# motion_sensor.net
KiCad netlist of a schematic drawn in Altium Designer
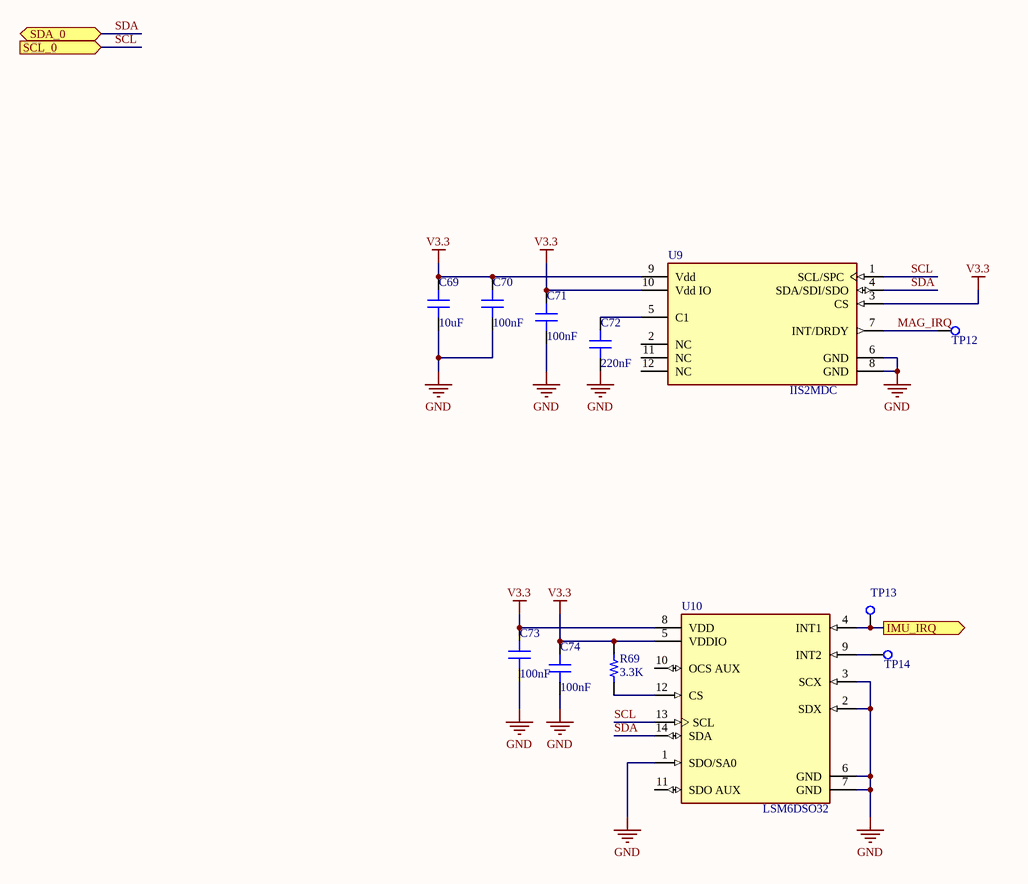
[diagram p0: motion_sensor.SchDoc]

(export (version "E")
  (design (tool "Eeschema 10.0.6"))
  (components
    (comp (ref "C69")
      (value "10uF")
      (footprint "CAP 0603_1608")
      (description "SMT Capacitor")
      (fields (field (name "MF") "Murata") (field (name "MP") "GRM188R61C106MAALD"))
      (libsource (lib "Capacitor") (part "Capacitor"))
    )
    (comp (ref "C70")
      (value "100nF")
      (footprint "CAP 0603_1608")
      (description "SMT Capacitor")
      (fields (field (name "MF") "TDK") (field (name "MP") "CGA3E2X7R1E104K080AA"))
      (libsource (lib "Capacitor") (part "Capacitor"))
    )
    (comp (ref "C71")
      (value "100nF")
      (footprint "CAP 0603_1608")
      (description "SMT Capacitor")
      (fields (field (name "MF") "TDK") (field (name "MP") "CGA3E2X7R1E104K080AA"))
      (libsource (lib "Capacitor") (part "Capacitor"))
    )
    (comp (ref "C72")
      (value "220nF")
      (footprint "CAP 0603_1608")
      (description "SMT Capacitor")
      (fields (field (name "MF") "Samsung") (field (name "MP") "CL10B224KO8NNNC"))
      (libsource (lib "Capacitor") (part "Capacitor"))
    )
    (comp (ref "C73")
      (value "100nF")
      (footprint "CAP 0603_1608")
      (description "SMT Capacitor")
      (fields (field (name "MF") "TDK") (field (name "MP") "CGA3E2X7R1E104K080AA"))
      (libsource (lib "Capacitor") (part "Capacitor"))
    )
    (comp (ref "C74")
      (value "100nF")
      (footprint "CAP 0603_1608")
      (description "SMT Capacitor")
      (fields (field (name "MF") "TDK") (field (name "MP") "CGA3E2X7R1E104K080AA"))
      (libsource (lib "Capacitor") (part "Capacitor"))
    )
    (comp (ref "R69")
      (value "3.3K")
      (footprint "RES 0603_1608")
      (description "SMT Resistor")
      (fields (field (name "MF") "YAGEO") (field (name "MP") "AC0603FR-073K3L"))
      (libsource (lib "Resistor") (part "Resistor"))
    )
    (comp (ref "TP12")
      (value "Test Point")
      (footprint "TPSMD_S1")
      (libsource (lib "Passive") (part "Test Point"))
    )
    (comp (ref "TP13")
      (value "Test Point")
      (footprint "TPSMD_S1")
      (libsource (lib "Passive") (part "Test Point"))
    )
    (comp (ref "TP14")
      (value "Test Point")
      (footprint "TPSMD_S1")
      (libsource (lib "Passive") (part "Test Point"))
    )
    (comp (ref "U9")
      (value "IIS2MDC")
      (footprint "STMicroelectronics_LGA-12-DM00170568_MFG")
      (fields (field (name "MF") "STMicroelectronics") (field (name "MP") "IIS2MDCTR"))
      (libsource (lib "IMU") (part "IIS2MDCTR"))
    )
    (comp (ref "U10")
      (value "LSM6DSO32")
      (footprint "STMicroelectronics_LGA-14L-DM00249496_MFG")
      (description "Inertial Measurement Unit, 6-axis, I2C, SPI, 1.7V-3.6V")
      (fields (field (name "MF") "STMicroelectronics") (field (name "MP") "LSM6DSO32TR"))
      (libsource (lib "IMU") (part "LSM6DSOTR"))
    )
  )
  (nets
    (net (code "1") (name "/IMU_IRQ") (class "Default")
      (node (ref "TP13") (pin "1") (pinfunction "TP_1") (pintype "passive"))
      (node (ref "U10") (pin "4") (pinfunction "INT1_4") (pintype "input"))
    )
    (net (code "2") (name "/MAG_IRQ") (class "Default")
      (node (ref "TP12") (pin "1") (pinfunction "TP_1") (pintype "passive"))
      (node (ref "U9") (pin "7") (pinfunction "INT/DRDY_7") (pintype "output"))
    )
    (net (code "3") (name "/SCL") (class "Default")
      (node (ref "U10") (pin "13") (pinfunction "SCL_13") (pintype "input"))
      (node (ref "U9") (pin "1") (pinfunction "SCL/SPC_1") (pintype "input"))
    )
    (net (code "4") (name "/SDA") (class "Default")
      (node (ref "U10") (pin "14") (pinfunction "SDA_14") (pintype "bidirectional"))
      (node (ref "U9") (pin "4") (pinfunction "SDA/SDI/SDO_4") (pintype "bidirectional"))
    )
    (net (code "5") (name "GND") (class "Default")
      (node (ref "C69") (pin "2") (pinfunction "2_2") (pintype "passive"))
      (node (ref "C70") (pin "2") (pinfunction "2_2") (pintype "passive"))
      (node (ref "C71") (pin "2") (pinfunction "2_2") (pintype "passive"))
      (node (ref "C72") (pin "2") (pinfunction "2_2") (pintype "passive"))
      (node (ref "C73") (pin "2") (pinfunction "2_2") (pintype "passive"))
      (node (ref "C74") (pin "2") (pinfunction "2_2") (pintype "passive"))
      (node (ref "U10") (pin "1") (pinfunction "SDO/SA0_1") (pintype "input"))
      (node (ref "U10") (pin "2") (pinfunction "SDX_2") (pintype "input"))
      (node (ref "U10") (pin "3") (pinfunction "SCX_3") (pintype "input"))
      (node (ref "U10") (pin "6") (pinfunction "GND_6") (pintype "power_in"))
      (node (ref "U10") (pin "7") (pinfunction "GND_7") (pintype "power_in"))
      (node (ref "U9") (pin "6") (pinfunction "GND_6") (pintype "power_in"))
      (node (ref "U9") (pin "8") (pinfunction "GND_8") (pintype "power_in"))
    )
    (net (code "6") (name "Net-(TP14-TP)") (class "Default")
      (node (ref "TP14") (pin "1") (pinfunction "TP_1") (pintype "passive"))
      (node (ref "U10") (pin "9") (pinfunction "INT2_9") (pintype "input"))
    )
    (net (code "7") (name "Net-(U9-C1)") (class "Default")
      (node (ref "C72") (pin "1") (pinfunction "1_1") (pintype "passive"))
      (node (ref "U9") (pin "5") (pinfunction "C1_5") (pintype "passive"))
    )
    (net (code "8") (name "Net-(U10-CS)") (class "Default")
      (node (ref "R69") (pin "1") (pinfunction "1_1") (pintype "passive"))
      (node (ref "U10") (pin "12") (pinfunction "CS_12") (pintype "input"))
    )
    (net (code "9") (name "V3.3") (class "Default")
      (node (ref "C69") (pin "1") (pinfunction "1_1") (pintype "passive"))
      (node (ref "C70") (pin "1") (pinfunction "1_1") (pintype "passive"))
      (node (ref "C71") (pin "1") (pinfunction "1_1") (pintype "passive"))
      (node (ref "C73") (pin "1") (pinfunction "1_1") (pintype "passive"))
      (node (ref "C74") (pin "1") (pinfunction "1_1") (pintype "passive"))
      (node (ref "R69") (pin "2") (pinfunction "2_2") (pintype "passive"))
      (node (ref "U10") (pin "5") (pinfunction "VDDIO_5") (pintype "power_in"))
      (node (ref "U10") (pin "8") (pinfunction "VDD_8") (pintype "power_in"))
      (node (ref "U9") (pin "10") (pinfunction "Vdd_IO_10") (pintype "power_in"))
      (node (ref "U9") (pin "3") (pinfunction "CS_3") (pintype "input"))
      (node (ref "U9") (pin "9") (pinfunction "Vdd_9") (pintype "power_in"))
    )
    (net (code "10") (name "unconnected-(U9-NC-Pad2)") (class "Default")
      (node (ref "U9") (pin "2") (pinfunction "NC_2") (pintype "passive"))
    )
    (net (code "11") (name "unconnected-(U9-NC-Pad11)") (class "Default")
      (node (ref "U9") (pin "11") (pinfunction "NC_11") (pintype "passive"))
    )
    (net (code "12") (name "unconnected-(U9-NC-Pad12)") (class "Default")
      (node (ref "U9") (pin "12") (pinfunction "NC_12") (pintype "passive"))
    )
    (net (code "13") (name "unconnected-(U10-OCS_AUX-Pad10)") (class "Default")
      (node (ref "U10") (pin "10") (pinfunction "OCS_AUX_10") (pintype "bidirectional"))
    )
    (net (code "14") (name "unconnected-(U10-SDO_AUX-Pad11)") (class "Default")
      (node (ref "U10") (pin "11") (pinfunction "SDO_AUX_11") (pintype "bidirectional"))
    )
  )
)
